# Sensor_Coup_Amp.net
KiCad netlist of a schematic drawn in Altium Designer
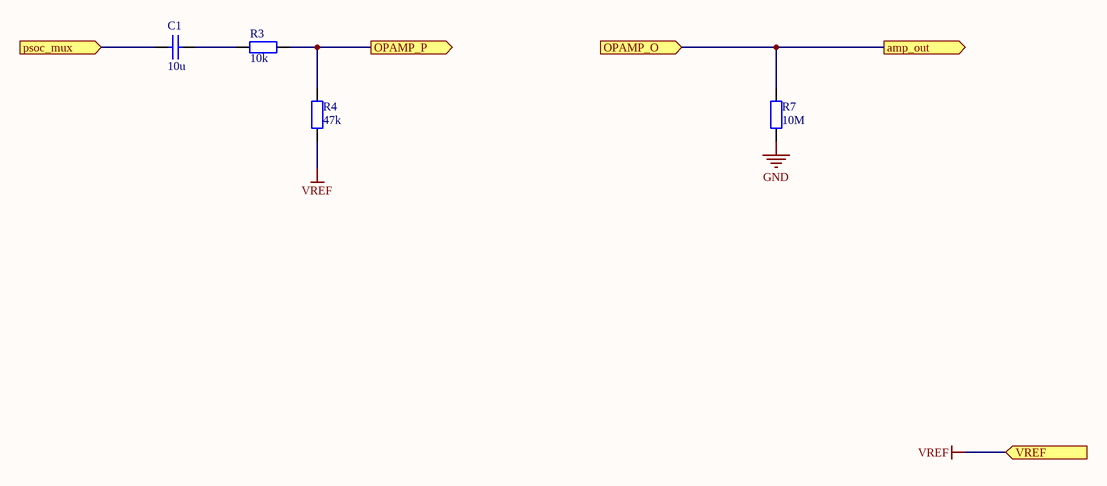
[diagram p0: Sensor_Coup_Amp.SchDoc]

(export (version "E")
  (design (tool "Eeschema 10.0.6"))
  (components
    (comp (ref "C1") (value "10u") (description "Capacitor") (libsource (lib "EceParts") (part "Cap")))
    (comp (ref "R3") (value "10k") (description "Resistor") (libsource (lib "") (part "Resistor_1")))
    (comp (ref "R4") (value "47k") (description "Resistor") (libsource (lib "EceParts") (part "Resistor")))
    (comp (ref "R7") (value "10M") (description "Resistor") (libsource (lib "EceParts") (part "Resistor")))
  )
  (nets
    (net (code "1") (name "/OPAMP_O") (class "Default")
      (node (ref "R7") (pin "2") (pinfunction "2_2") (pintype "passive"))
    )
    (net (code "2") (name "/OPAMP_P") (class "Default")
      (node (ref "R3") (pin "2") (pinfunction "2_2") (pintype "passive"))
      (node (ref "R4") (pin "2") (pinfunction "2_2") (pintype "passive"))
    )
    (net (code "3") (name "/psoc_mux") (class "Default")
      (node (ref "C1") (pin "1") (pinfunction "1_1") (pintype "passive"))
    )
    (net (code "4") (name "GND") (class "Default")
      (node (ref "R7") (pin "1") (pinfunction "1_1") (pintype "passive"))
    )
    (net (code "5") (name "Net-(C1-Pad2)") (class "Default")
      (node (ref "C1") (pin "2") (pinfunction "2_2") (pintype "passive"))
      (node (ref "R3") (pin "1") (pinfunction "1_1") (pintype "passive"))
    )
    (net (code "6") (name "VREF") (class "Default")
      (node (ref "R4") (pin "1") (pinfunction "1_1") (pintype "passive"))
    )
  )
)
